# STML451RE_Buck_HSI.net
KiCad netlist of a schematic drawn in EAGLE
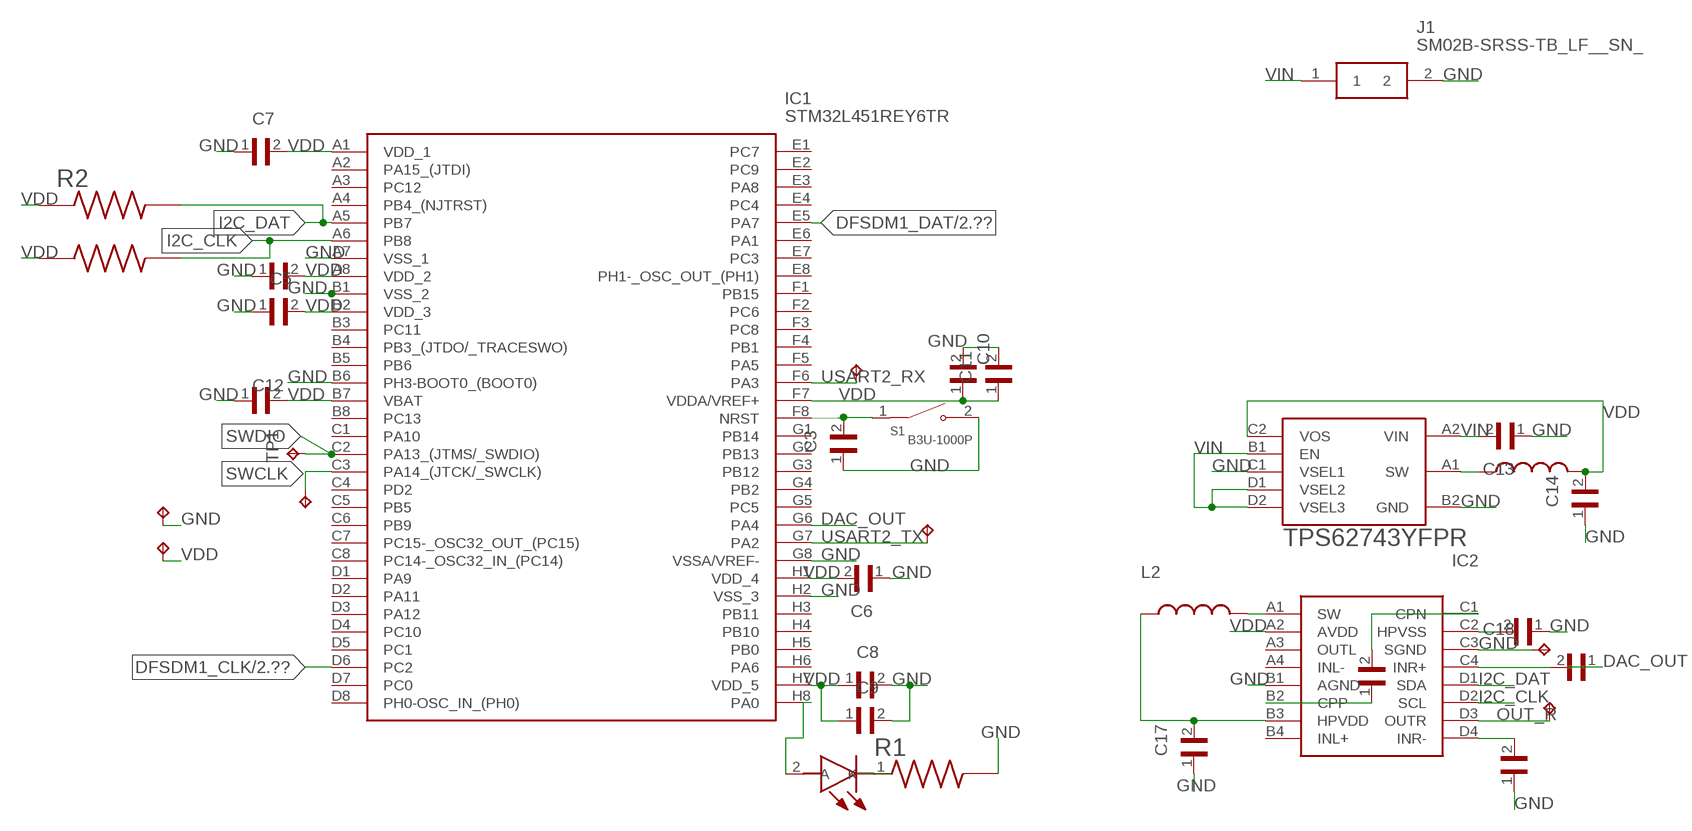
[diagram p0: schematic, sheet 1]
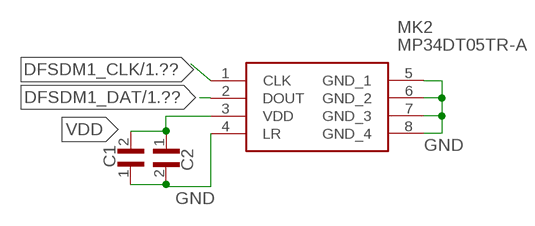
[diagram p1: schematic, sheet 2]

(export (version "E")
  (design (tool "Eeschema 10.0.6"))
  (components
    (comp (ref "C3")
      (value "GRM033C80J104KE15D")
      (footprint "eagle-import:CAPC0603X33N")
      (fields (field (name "DIGI-KEY_PART_NUMBER") "490-10390-1-ND") (field (name "MF") "Murata Electronics"))
      (libsource (lib "eagle-import") (part "GRM033C80J104KE15D"))
    )
    (comp (ref "C4")
      (value "GRM033C80J104KE15D")
      (footprint "eagle-import:CAPC0603X33N")
      (fields (field (name "DIGI-KEY_PART_NUMBER") "490-10390-1-ND") (field (name "MF") "Murata Electronics"))
      (libsource (lib "eagle-import") (part "GRM033C80J104KE15D"))
    )
    (comp (ref "C5")
      (value "GRM033C80J104KE15D")
      (footprint "eagle-import:CAPC0603X33N")
      (fields (field (name "DIGI-KEY_PART_NUMBER") "490-10390-1-ND") (field (name "MF") "Murata Electronics"))
      (libsource (lib "eagle-import") (part "GRM033C80J104KE15D"))
    )
    (comp (ref "C6")
      (value "GRM033C80J104KE15D")
      (footprint "eagle-import:CAPC0603X33N")
      (fields (field (name "DIGI-KEY_PART_NUMBER") "490-10390-1-ND") (field (name "MF") "Murata Electronics"))
      (libsource (lib "eagle-import") (part "GRM033C80J104KE15D"))
    )
    (comp (ref "C7")
      (value "GRM033C80J104KE15D")
      (footprint "eagle-import:CAPC0603X33N")
      (fields (field (name "DIGI-KEY_PART_NUMBER") "490-10390-1-ND") (field (name "MF") "Murata Electronics"))
      (libsource (lib "eagle-import") (part "GRM033C80J104KE15D"))
    )
    (comp (ref "C8")
      (value "GRM033C80J104KE15D")
      (footprint "eagle-import:CAPC0603X33N")
      (fields (field (name "DIGI-KEY_PART_NUMBER") "490-10390-1-ND") (field (name "MF") "Murata Electronics"))
      (libsource (lib "eagle-import") (part "GRM033C80J104KE15D"))
    )
    (comp (ref "C9")
      (value "GRM155R60J475ME47D")
      (footprint "eagle-import:CAPC1005X60N")
      (fields (field (name "DIGI-KEY_PART_NUMBER") "490-5915-1-ND") (field (name "MF") "Murata"))
      (libsource (lib "eagle-import") (part "GRM155R60J475ME47D"))
    )
    (comp (ref "C10")
      (value "GRM033C80J104KE15D")
      (footprint "eagle-import:CAPC0603X33N")
      (fields (field (name "DIGI-KEY_PART_NUMBER") "490-10390-1-ND") (field (name "MF") "Murata Electronics"))
      (libsource (lib "eagle-import") (part "GRM033C80J104KE15D"))
    )
    (comp (ref "C11")
      (value "JMK105C6105KV-F")
      (footprint "eagle-import:CAPC1005X55N")
      (fields (field (name "DIGI-KEY_PART_NUMBER") "587-3381-1-ND") (field (name "MF") "Taiyo Yuden"))
      (libsource (lib "eagle-import") (part "JMK105C6105KV-F"))
    )
    (comp (ref "C12")
      (value "GRM033C80J104KE15D")
      (footprint "eagle-import:CAPC0603X33N")
      (fields (field (name "DIGI-KEY_PART_NUMBER") "490-10390-1-ND") (field (name "MF") "Murata Electronics"))
      (libsource (lib "eagle-import") (part "GRM033C80J104KE15D"))
    )
    (comp (ref "C13")
      (value "GRM155R60J475ME47D")
      (footprint "eagle-import:CAPC1005X60N")
      (fields (field (name "DIGI-KEY_PART_NUMBER") "490-5915-1-ND") (field (name "MF") "Murata"))
      (libsource (lib "eagle-import") (part "GRM155R60J475ME47D"))
    )
    (comp (ref "C14")
      (value "GRM155R60J106ME15D")
      (footprint "eagle-import:CAPC1005X65N")
      (fields (field (name "DIGI-KEY_PART_NUMBER") "490-13238-1-ND") (field (name "MF") "Murata"))
      (libsource (lib "eagle-import") (part "GRM155R60J106ME15D"))
    )
    (comp (ref "C17")
      (value "GRM155R60J225KE95D")
      (footprint "eagle-import:CAPC1005X55N")
      (fields (field (name "DIGI-KEY_PART_NUMBER") "490-12532-1-ND") (field (name "MF") "Murata"))
      (libsource (lib "eagle-import") (part "GRM155R60J225KE95D"))
    )
    (comp (ref "C18")
      (value "GRM155R60J225KE95D")
      (footprint "eagle-import:CAPC1005X55N")
      (fields (field (name "DIGI-KEY_PART_NUMBER") "490-12532-1-ND") (field (name "MF") "Murata"))
      (libsource (lib "eagle-import") (part "GRM155R60J225KE95D"))
    )
    (comp (ref "C19")
      (value "JMK105C6105KV-F")
      (footprint "eagle-import:CAPC1005X55N")
      (fields (field (name "DIGI-KEY_PART_NUMBER") "587-3381-1-ND") (field (name "MF") "Taiyo Yuden"))
      (libsource (lib "eagle-import") (part "JMK105C6105KV-F"))
    )
    (comp (ref "C20")
      (value "JMK105C6105KV-F")
      (footprint "eagle-import:CAPC1005X55N")
      (fields (field (name "DIGI-KEY_PART_NUMBER") "587-3381-1-ND") (field (name "MF") "Taiyo Yuden"))
      (libsource (lib "eagle-import") (part "JMK105C6105KV-F"))
    )
    (comp (ref "C21")
      (value "JMK105C6105KV-F")
      (footprint "eagle-import:CAPC1005X55N")
      (fields (field (name "DIGI-KEY_PART_NUMBER") "587-3381-1-ND") (field (name "MF") "Taiyo Yuden"))
      (libsource (lib "eagle-import") (part "JMK105C6105KV-F"))
    )
    (comp (ref "IC1")
      (value "STM32L451REY6TR")
      (footprint "eagle-import:BGA64C40P8X8_336X366X58")
      (fields (field (name "MOUSER_PART_NUMBER") "511-STM32L451REY6TR"))
      (libsource (lib "eagle-import") (part "STM32L451REY6TR"))
    )
    (comp (ref "IC2")
      (value "TPA6140A2YFFT")
      (footprint "eagle-import:BGA16C40P4X4_156X156X63")
      (fields (field (name "MOUSER_PART_NUMBER") "595-TPA6140A2YFFT"))
      (libsource (lib "eagle-import") (part "TPA6140A2YFFT"))
    )
    (comp (ref "J1")
      (value "SM02B-SRSS-TB_LF__SN_")
      (footprint "eagle-import:SM02B-SRSS-TB")
      (fields (field (name "ARROW_PART_NUMBER") "SM02B-SRSS-TB(LF)(SN)"))
      (libsource (lib "eagle-import") (part "SM02B-SRSS-TB_LF__SN_"))
    )
    (comp (ref "L1")
      (value "1285AS-H-2R2M=P2")
      (footprint "eagle-import:INDC2016X100N")
      (fields (field (name "DIGI-KEY_PART_NUMBER") "490-10600-1-ND") (field (name "MF") "Murata Electronics"))
      (libsource (lib "eagle-import") (part "1285AS-H-2R2M=P2"))
    )
    (comp (ref "L2")
      (value "LQM21PN2R2MC0D")
      (footprint "eagle-import:INDC2012X55N")
      (fields (field (name "DIGI-KEY_PART_NUMBER") "490-4994-1-ND") (field (name "MF") "Murata"))
      (libsource (lib "eagle-import") (part "LQM21PN2R2MC0D"))
    )
    (comp (ref "LED1")
      (value "VLMS1500-GS08")
      (footprint "eagle-import:VLMG1500GS08")
      (fields (field (name "MOUSER_PART_NUMBER") "78-VLMS1500-GS08"))
      (libsource (lib "eagle-import") (part "VLMS1500-GS08"))
    )
    (comp (ref "R1")
      (value "CRCW02012K20FKED")
      (footprint "eagle-import:RESC0603X28N")
      (fields (field (name "DIGI-KEY_PART_NUMBER") "541-2.20KAABCT-ND") (field (name "MF") "Vishay"))
      (libsource (lib "eagle-import") (part "CRCW02012K20FKED"))
    )
    (comp (ref "R2")
      (value "ERA-2AEB122X")
      (footprint "eagle-import:RESC1005X40N")
      (fields (field (name "DIGI-KEY_PART_NUMBER") "P1.2KDCCT-ND") (field (name "MF") "Panasonic"))
      (libsource (lib "eagle-import") (part "ERA-2AEB122X"))
    )
    (comp (ref "R3")
      (value "ERA-2AEB122X")
      (footprint "eagle-import:RESC1005X40N")
      (fields (field (name "DIGI-KEY_PART_NUMBER") "P1.2KDCCT-ND") (field (name "MF") "Panasonic"))
      (libsource (lib "eagle-import") (part "ERA-2AEB122X"))
    )
    (comp (ref "S1")
      (value "B3U-1000P")
      (footprint "eagle-import:SW_B3U-1000P")
      (fields (field (name "DIGI-KEY_PART_NUMBER") "SW1020CT-ND") (field (name "MF") "Omron"))
      (libsource (lib "eagle-import") (part "B3U-1000P"))
    )
    (comp (ref "TP1")
      (value "TPTP11R")
      (footprint "eagle-import:TP11R")
      (libsource (lib "eagle-import") (part "TPTP11R"))
    )
    (comp (ref "TP2")
      (value "TPTP11R")
      (footprint "eagle-import:TP11R")
      (libsource (lib "eagle-import") (part "TPTP11R"))
    )
    (comp (ref "TP3")
      (value "TPTP11R")
      (footprint "eagle-import:TP11R")
      (libsource (lib "eagle-import") (part "TPTP11R"))
    )
    (comp (ref "TP4")
      (value "TPTP11R")
      (footprint "eagle-import:TP11R")
      (libsource (lib "eagle-import") (part "TPTP11R"))
    )
    (comp (ref "TP5")
      (value "TPTP11R")
      (footprint "eagle-import:TP11R")
      (libsource (lib "eagle-import") (part "TPTP11R"))
    )
    (comp (ref "TP6")
      (value "TPTP11R")
      (footprint "eagle-import:TP11R")
      (libsource (lib "eagle-import") (part "TPTP11R"))
    )
    (comp (ref "TP7")
      (value "TPTP11R")
      (footprint "eagle-import:TP11R")
      (libsource (lib "eagle-import") (part "TPTP11R"))
    )
    (comp (ref "TP8")
      (value "TPTP11R")
      (footprint "eagle-import:TP11R")
      (libsource (lib "eagle-import") (part "TPTP11R"))
    )
    (comp (ref "U1")
      (value "TPS62743YFPR")
      (footprint "eagle-import:BGA8N40P2X4_87X156X50")
      (fields (field (name "DIGI-KEY_PART_NUMBER") "296-42392-1-ND") (field (name "MF") "Texas Instruments"))
      (libsource (lib "eagle-import") (part "TPS62743YFPR"))
    )
    (comp (ref "C1")
      (value "GRM033C80J104KE15D")
      (footprint "eagle-import:CAPC0603X33N")
      (fields (field (name "DIGI-KEY_PART_NUMBER") "490-10390-1-ND") (field (name "MF") "Murata Electronics"))
      (libsource (lib "eagle-import") (part "GRM033C80J104KE15D"))
    )
    (comp (ref "C2")
      (value "JMK105C6105KV-F")
      (footprint "eagle-import:CAPC1005X55N")
      (fields (field (name "DIGI-KEY_PART_NUMBER") "587-3381-1-ND") (field (name "MF") "Taiyo Yuden"))
      (libsource (lib "eagle-import") (part "JMK105C6105KV-F"))
    )
    (comp (ref "MK2")
      (value "MP34DT05TR-A")
      (footprint "eagle-import:MP34DT05TRA")
      (fields (field (name "MOUSER_PART_NUMBER") "511-MP34DT05TR-A"))
      (libsource (lib "eagle-import") (part "MP34DT05TR-A"))
    )
  )
  (nets
    (net (code "1") (name "DAC_OUT") (class "Default")
      (node (ref "C21") (pin "1") (pinfunction "1_1") (pintype "passive"))
      (node (ref "IC1") (pin "G6") (pinfunction "PA4_G6") (pintype "bidirectional"))
    )
    (net (code "2") (name "DFSDM1_CLK") (class "Default")
      (node (ref "IC1") (pin "D6") (pinfunction "PC2_D6") (pintype "bidirectional"))
      (node (ref "MK2") (pin "1") (pinfunction "CLK_1") (pintype "bidirectional"))
    )
    (net (code "3") (name "DFSDM1_DAT") (class "Default")
      (node (ref "IC1") (pin "E5") (pinfunction "PA7_E5") (pintype "bidirectional"))
      (node (ref "MK2") (pin "2") (pinfunction "DOUT_2") (pintype "bidirectional"))
    )
    (net (code "4") (name "GND") (class "Default")
      (node (ref "C1") (pin "1") (pinfunction "1_1") (pintype "passive"))
      (node (ref "C10") (pin "2") (pinfunction "2_2") (pintype "passive"))
      (node (ref "C11") (pin "2") (pinfunction "2_2") (pintype "passive"))
      (node (ref "C12") (pin "1") (pinfunction "1_1") (pintype "passive"))
      (node (ref "C13") (pin "1") (pinfunction "1_1") (pintype "passive"))
      (node (ref "C14") (pin "1") (pinfunction "1_1") (pintype "passive"))
      (node (ref "C17") (pin "1") (pinfunction "1_1") (pintype "passive"))
      (node (ref "C18") (pin "1") (pinfunction "1_1") (pintype "passive"))
      (node (ref "C2") (pin "2") (pinfunction "2_2") (pintype "passive"))
      (node (ref "C20") (pin "1") (pinfunction "1_1") (pintype "passive"))
      (node (ref "C3") (pin "1") (pinfunction "1_1") (pintype "passive"))
      (node (ref "C4") (pin "1") (pinfunction "1_1") (pintype "passive"))
      (node (ref "C5") (pin "1") (pinfunction "1_1") (pintype "passive"))
      (node (ref "C6") (pin "1") (pinfunction "1_1") (pintype "passive"))
      (node (ref "C7") (pin "1") (pinfunction "1_1") (pintype "passive"))
      (node (ref "C8") (pin "2") (pinfunction "2_2") (pintype "passive"))
      (node (ref "C9") (pin "2") (pinfunction "2_2") (pintype "passive"))
      (node (ref "IC1") (pin "A7") (pinfunction "VSS_1_A7") (pintype "bidirectional"))
      (node (ref "IC1") (pin "B1") (pinfunction "VSS_2_B1") (pintype "bidirectional"))
      (node (ref "IC1") (pin "B6") (pinfunction "PH3-BOOT0_(BOOT0)_B6") (pintype "bidirectional"))
      (node (ref "IC1") (pin "G8") (pinfunction "VSSA/VREF-_G8") (pintype "bidirectional"))
      (node (ref "IC1") (pin "H2") (pinfunction "VSS_3_H2") (pintype "bidirectional"))
      (node (ref "IC2") (pin "B1") (pinfunction "AGND_B1") (pintype "bidirectional"))
      (node (ref "IC2") (pin "C3") (pinfunction "SGND_C3") (pintype "bidirectional"))
      (node (ref "J1") (pin "2") (pinfunction "2_2") (pintype "bidirectional"))
      (node (ref "MK2") (pin "4") (pinfunction "LR_4") (pintype "bidirectional"))
      (node (ref "MK2") (pin "5") (pinfunction "GND_1_5") (pintype "bidirectional"))
      (node (ref "MK2") (pin "6") (pinfunction "GND_2_6") (pintype "bidirectional"))
      (node (ref "MK2") (pin "7") (pinfunction "GND_3_7") (pintype "bidirectional"))
      (node (ref "MK2") (pin "8") (pinfunction "GND_4_8") (pintype "bidirectional"))
      (node (ref "R1") (pin "2") (pinfunction "2_2") (pintype "passive"))
      (node (ref "S1") (pin "2") (pinfunction "2_2") (pintype "passive"))
      (node (ref "TP3") (pin "TP") (pinfunction "TP_TP") (pintype "input"))
      (node (ref "TP8") (pin "TP") (pinfunction "TP_TP") (pintype "input"))
      (node (ref "U1") (pin "B2") (pinfunction "GND_B2") (pintype "passive"))
      (node (ref "U1") (pin "C1") (pinfunction "VSEL1_C1") (pintype "input"))
    )
    (net (code "5") (name "I2C_CLK") (class "Default")
      (node (ref "IC1") (pin "A6") (pinfunction "PB8_A6") (pintype "bidirectional"))
      (node (ref "IC2") (pin "D2") (pinfunction "SCL_D2") (pintype "bidirectional"))
      (node (ref "R3") (pin "2") (pinfunction "2_2") (pintype "passive"))
    )
    (net (code "6") (name "I2C_DAT") (class "Default")
      (node (ref "IC1") (pin "A5") (pinfunction "PB7_A5") (pintype "bidirectional"))
      (node (ref "IC2") (pin "D1") (pinfunction "SDA_D1") (pintype "bidirectional"))
      (node (ref "R2") (pin "2") (pinfunction "2_2") (pintype "passive"))
    )
    (net (code "7") (name "Net-(C3-Pad2)") (class "Default")
      (node (ref "C3") (pin "2") (pinfunction "2_2") (pintype "passive"))
      (node (ref "S1") (pin "1") (pinfunction "1_1") (pintype "passive"))
    )
    (net (code "8") (name "Net-(IC1-PA0)") (class "Default")
      (node (ref "IC1") (pin "H8") (pinfunction "PA0_H8") (pintype "bidirectional"))
      (node (ref "LED1") (pin "2") (pinfunction "A_2") (pintype "bidirectional"))
    )
    (net (code "9") (name "Net-(IC2-CPN)") (class "Default")
      (node (ref "C19") (pin "2") (pinfunction "2_2") (pintype "passive"))
      (node (ref "IC2") (pin "C1") (pinfunction "CPN_C1") (pintype "bidirectional"))
    )
    (net (code "10") (name "Net-(IC2-CPP)") (class "Default")
      (node (ref "C19") (pin "1") (pinfunction "1_1") (pintype "passive"))
      (node (ref "IC2") (pin "B2") (pinfunction "CPP_B2") (pintype "bidirectional"))
    )
    (net (code "11") (name "Net-(IC2-HPVDD)") (class "Default")
      (node (ref "C17") (pin "2") (pinfunction "2_2") (pintype "passive"))
      (node (ref "IC2") (pin "B3") (pinfunction "HPVDD_B3") (pintype "bidirectional"))
      (node (ref "L2") (pin "1") (pinfunction "1_1") (pintype "passive"))
    )
    (net (code "12") (name "Net-(IC2-HPVSS)") (class "Default")
      (node (ref "C18") (pin "2") (pinfunction "2_2") (pintype "passive"))
      (node (ref "IC2") (pin "C2") (pinfunction "HPVSS_C2") (pintype "bidirectional"))
    )
    (net (code "13") (name "Net-(IC2-INR+)") (class "Default")
      (node (ref "C21") (pin "2") (pinfunction "2_2") (pintype "passive"))
      (node (ref "IC2") (pin "C4") (pinfunction "INR+_C4") (pintype "bidirectional"))
    )
    (net (code "14") (name "Net-(IC2-INR-)") (class "Default")
      (node (ref "C20") (pin "2") (pinfunction "2_2") (pintype "passive"))
      (node (ref "IC2") (pin "D4") (pinfunction "INR-_D4") (pintype "bidirectional"))
    )
    (net (code "15") (name "Net-(IC2-SW)") (class "Default")
      (node (ref "IC2") (pin "A1") (pinfunction "SW_A1") (pintype "bidirectional"))
      (node (ref "L2") (pin "2") (pinfunction "2_2") (pintype "passive"))
    )
    (net (code "16") (name "Net-(LED1-K)") (class "Default")
      (node (ref "LED1") (pin "1") (pinfunction "K_1") (pintype "bidirectional"))
      (node (ref "R1") (pin "1") (pinfunction "1_1") (pintype "passive"))
    )
    (net (code "17") (name "Net-(U1-SW)") (class "Default")
      (node (ref "L1") (pin "1") (pinfunction "1_1") (pintype "passive"))
      (node (ref "U1") (pin "A1") (pinfunction "SW_A1") (pintype "output"))
    )
    (net (code "18") (name "OUT_R") (class "Default")
      (node (ref "IC2") (pin "D3") (pinfunction "OUTR_D3") (pintype "bidirectional"))
      (node (ref "TP7") (pin "TP") (pinfunction "TP_TP") (pintype "input"))
    )
    (net (code "19") (name "SWCLK") (class "Default")
      (node (ref "IC1") (pin "C3") (pinfunction "PA14_(JTCK/_SWCLK)_C3") (pintype "bidirectional"))
      (node (ref "TP2") (pin "TP") (pinfunction "TP_TP") (pintype "input"))
    )
    (net (code "20") (name "SWDIO") (class "Default")
      (node (ref "IC1") (pin "C2") (pinfunction "PA13_(JTMS/_SWDIO)_C2") (pintype "bidirectional"))
      (node (ref "TP1") (pin "TP") (pinfunction "TP_TP") (pintype "input"))
    )
    (net (code "21") (name "USART2_RX") (class "Default")
      (node (ref "IC1") (pin "F6") (pinfunction "PA3_F6") (pintype "bidirectional"))
      (node (ref "TP6") (pin "TP") (pinfunction "TP_TP") (pintype "input"))
    )
    (net (code "22") (name "USART2_TX") (class "Default")
      (node (ref "IC1") (pin "G7") (pinfunction "PA2_G7") (pintype "bidirectional"))
      (node (ref "TP5") (pin "TP") (pinfunction "TP_TP") (pintype "input"))
    )
    (net (code "23") (name "VDD") (class "Default")
      (node (ref "C1") (pin "2") (pinfunction "2_2") (pintype "passive"))
      (node (ref "C10") (pin "1") (pinfunction "1_1") (pintype "passive"))
      (node (ref "C11") (pin "1") (pinfunction "1_1") (pintype "passive"))
      (node (ref "C12") (pin "2") (pinfunction "2_2") (pintype "passive"))
      (node (ref "C14") (pin "2") (pinfunction "2_2") (pintype "passive"))
      (node (ref "C2") (pin "1") (pinfunction "1_1") (pintype "passive"))
      (node (ref "C4") (pin "2") (pinfunction "2_2") (pintype "passive"))
      (node (ref "C5") (pin "2") (pinfunction "2_2") (pintype "passive"))
      (node (ref "C6") (pin "2") (pinfunction "2_2") (pintype "passive"))
      (node (ref "C7") (pin "2") (pinfunction "2_2") (pintype "passive"))
      (node (ref "C8") (pin "1") (pinfunction "1_1") (pintype "passive"))
      (node (ref "C9") (pin "1") (pinfunction "1_1") (pintype "passive"))
      (node (ref "IC1") (pin "A1") (pinfunction "VDD_1_A1") (pintype "bidirectional"))
      (node (ref "IC1") (pin "A8") (pinfunction "VDD_2_A8") (pintype "bidirectional"))
      (node (ref "IC1") (pin "B2") (pinfunction "VDD_3_B2") (pintype "bidirectional"))
      (node (ref "IC1") (pin "B7") (pinfunction "VBAT_B7") (pintype "bidirectional"))
      (node (ref "IC1") (pin "F7") (pinfunction "VDDA/VREF+_F7") (pintype "bidirectional"))
      (node (ref "IC1") (pin "H1") (pinfunction "VDD_4_H1") (pintype "bidirectional"))
      (node (ref "IC1") (pin "H7") (pinfunction "VDD_5_H7") (pintype "bidirectional"))
      (node (ref "IC2") (pin "A2") (pinfunction "AVDD_A2") (pintype "bidirectional"))
      (node (ref "L1") (pin "2") (pinfunction "2_2") (pintype "passive"))
      (node (ref "MK2") (pin "3") (pinfunction "VDD_3") (pintype "bidirectional"))
      (node (ref "R2") (pin "1") (pinfunction "1_1") (pintype "passive"))
      (node (ref "R3") (pin "1") (pinfunction "1_1") (pintype "passive"))
      (node (ref "TP4") (pin "TP") (pinfunction "TP_TP") (pintype "input"))
      (node (ref "U1") (pin "C2") (pinfunction "VOS_C2") (pintype "input"))
    )
    (net (code "24") (name "VIN") (class "Default")
      (node (ref "C13") (pin "2") (pinfunction "2_2") (pintype "passive"))
      (node (ref "J1") (pin "1") (pinfunction "1_1") (pintype "bidirectional"))
      (node (ref "U1") (pin "A2") (pinfunction "VIN_A2") (pintype "power_in"))
      (node (ref "U1") (pin "B1") (pinfunction "EN_B1") (pintype "input"))
      (node (ref "U1") (pin "D1") (pinfunction "VSEL2_D1") (pintype "input"))
      (node (ref "U1") (pin "D2") (pinfunction "VSEL3_D2") (pintype "input"))
    )
    (net (code "25") (name "unconnected-(IC1-NRST-PadF8)") (class "Default")
      (node (ref "IC1") (pin "F8") (pinfunction "NRST_F8") (pintype "bidirectional"))
    )
    (net (code "26") (name "unconnected-(IC1-PA1-PadE6)") (class "Default")
      (node (ref "IC1") (pin "E6") (pinfunction "PA1_E6") (pintype "bidirectional"))
    )
    (net (code "27") (name "unconnected-(IC1-PA5-PadF5)") (class "Default")
      (node (ref "IC1") (pin "F5") (pinfunction "PA5_F5") (pintype "bidirectional"))
    )
    (net (code "28") (name "unconnected-(IC1-PA6-PadH6)") (class "Default")
      (node (ref "IC1") (pin "H6") (pinfunction "PA6_H6") (pintype "bidirectional"))
    )
    (net (code "29") (name "unconnected-(IC1-PA8-PadE3)") (class "Default")
      (node (ref "IC1") (pin "E3") (pinfunction "PA8_E3") (pintype "bidirectional"))
    )
    (net (code "30") (name "unconnected-(IC1-PA9-PadD1)") (class "Default")
      (node (ref "IC1") (pin "D1") (pinfunction "PA9_D1") (pintype "bidirectional"))
    )
    (net (code "31") (name "unconnected-(IC1-PA10-PadC1)") (class "Default")
      (node (ref "IC1") (pin "C1") (pinfunction "PA10_C1") (pintype "bidirectional"))
    )
    (net (code "32") (name "unconnected-(IC1-PA11-PadD2)") (class "Default")
      (node (ref "IC1") (pin "D2") (pinfunction "PA11_D2") (pintype "bidirectional"))
    )
    (net (code "33") (name "unconnected-(IC1-PA12-PadD3)") (class "Default")
      (node (ref "IC1") (pin "D3") (pinfunction "PA12_D3") (pintype "bidirectional"))
    )
    (net (code "34") (name "unconnected-(IC1-PA15_(JTDI)-PadA2)") (class "Default")
      (node (ref "IC1") (pin "A2") (pinfunction "PA15_(JTDI)_A2") (pintype "bidirectional"))
    )
    (net (code "35") (name "unconnected-(IC1-PB0-PadH5)") (class "Default")
      (node (ref "IC1") (pin "H5") (pinfunction "PB0_H5") (pintype "bidirectional"))
    )
    (net (code "36") (name "unconnected-(IC1-PB1-PadF4)") (class "Default")
      (node (ref "IC1") (pin "F4") (pinfunction "PB1_F4") (pintype "bidirectional"))
    )
    (net (code "37") (name "unconnected-(IC1-PB2-PadG4)") (class "Default")
      (node (ref "IC1") (pin "G4") (pinfunction "PB2_G4") (pintype "bidirectional"))
    )
    (net (code "38") (name "unconnected-(IC1-PB3_(JTDO{slash}_TRACESWO)-PadB4)") (class "Default")
      (node (ref "IC1") (pin "B4") (pinfunction "PB3_(JTDO/_TRACESWO)_B4") (pintype "bidirectional"))
    )
    (net (code "39") (name "unconnected-(IC1-PB4_(NJTRST)-PadA4)") (class "Default")
      (node (ref "IC1") (pin "A4") (pinfunction "PB4_(NJTRST)_A4") (pintype "bidirectional"))
    )
    (net (code "40") (name "unconnected-(IC1-PB5-PadC5)") (class "Default")
      (node (ref "IC1") (pin "C5") (pinfunction "PB5_C5") (pintype "bidirectional"))
    )
    (net (code "41") (name "unconnected-(IC1-PB6-PadB5)") (class "Default")
      (node (ref "IC1") (pin "B5") (pinfunction "PB6_B5") (pintype "bidirectional"))
    )
    (net (code "42") (name "unconnected-(IC1-PB9-PadC6)") (class "Default")
      (node (ref "IC1") (pin "C6") (pinfunction "PB9_C6") (pintype "bidirectional"))
    )
    (net (code "43") (name "unconnected-(IC1-PB10-PadH4)") (class "Default")
      (node (ref "IC1") (pin "H4") (pinfunction "PB10_H4") (pintype "bidirectional"))
    )
    (net (code "44") (name "unconnected-(IC1-PB11-PadH3)") (class "Default")
      (node (ref "IC1") (pin "H3") (pinfunction "PB11_H3") (pintype "bidirectional"))
    )
    (net (code "45") (name "unconnected-(IC1-PB12-PadG3)") (class "Default")
      (node (ref "IC1") (pin "G3") (pinfunction "PB12_G3") (pintype "bidirectional"))
    )
    (net (code "46") (name "unconnected-(IC1-PB13-PadG2)") (class "Default")
      (node (ref "IC1") (pin "G2") (pinfunction "PB13_G2") (pintype "bidirectional"))
    )
    (net (code "47") (name "unconnected-(IC1-PB14-PadG1)") (class "Default")
      (node (ref "IC1") (pin "G1") (pinfunction "PB14_G1") (pintype "bidirectional"))
    )
    (net (code "48") (name "unconnected-(IC1-PB15-PadF1)") (class "Default")
      (node (ref "IC1") (pin "F1") (pinfunction "PB15_F1") (pintype "bidirectional"))
    )
    (net (code "49") (name "unconnected-(IC1-PC0-PadD7)") (class "Default")
      (node (ref "IC1") (pin "D7") (pinfunction "PC0_D7") (pintype "bidirectional"))
    )
    (net (code "50") (name "unconnected-(IC1-PC1-PadD5)") (class "Default")
      (node (ref "IC1") (pin "D5") (pinfunction "PC1_D5") (pintype "bidirectional"))
    )
    (net (code "51") (name "unconnected-(IC1-PC3-PadE7)") (class "Default")
      (node (ref "IC1") (pin "E7") (pinfunction "PC3_E7") (pintype "bidirectional"))
    )
    (net (code "52") (name "unconnected-(IC1-PC4-PadE4)") (class "Default")
      (node (ref "IC1") (pin "E4") (pinfunction "PC4_E4") (pintype "bidirectional"))
    )
    (net (code "53") (name "unconnected-(IC1-PC5-PadG5)") (class "Default")
      (node (ref "IC1") (pin "G5") (pinfunction "PC5_G5") (pintype "bidirectional"))
    )
    (net (code "54") (name "unconnected-(IC1-PC6-PadF2)") (class "Default")
      (node (ref "IC1") (pin "F2") (pinfunction "PC6_F2") (pintype "bidirectional"))
    )
    (net (code "55") (name "unconnected-(IC1-PC7-PadE1)") (class "Default")
      (node (ref "IC1") (pin "E1") (pinfunction "PC7_E1") (pintype "bidirectional"))
    )
    (net (code "56") (name "unconnected-(IC1-PC8-PadF3)") (class "Default")
      (node (ref "IC1") (pin "F3") (pinfunction "PC8_F3") (pintype "bidirectional"))
    )
    (net (code "57") (name "unconnected-(IC1-PC9-PadE2)") (class "Default")
      (node (ref "IC1") (pin "E2") (pinfunction "PC9_E2") (pintype "bidirectional"))
    )
    (net (code "58") (name "unconnected-(IC1-PC10-PadD4)") (class "Default")
      (node (ref "IC1") (pin "D4") (pinfunction "PC10_D4") (pintype "bidirectional"))
    )
    (net (code "59") (name "unconnected-(IC1-PC11-PadB3)") (class "Default")
      (node (ref "IC1") (pin "B3") (pinfunction "PC11_B3") (pintype "bidirectional"))
    )
    (net (code "60") (name "unconnected-(IC1-PC12-PadA3)") (class "Default")
      (node (ref "IC1") (pin "A3") (pinfunction "PC12_A3") (pintype "bidirectional"))
    )
    (net (code "61") (name "unconnected-(IC1-PC13-PadB8)") (class "Default")
      (node (ref "IC1") (pin "B8") (pinfunction "PC13_B8") (pintype "bidirectional"))
    )
    (net (code "62") (name "unconnected-(IC1-PC14-_OSC32_IN_(PC14)-PadC8)") (class "Default")
      (node (ref "IC1") (pin "C8") (pinfunction "PC14-_OSC32_IN_(PC14)_C8") (pintype "bidirectional"))
    )
    (net (code "63") (name "unconnected-(IC1-PC15-_OSC32_OUT_(PC15)-PadC7)") (class "Default")
      (node (ref "IC1") (pin "C7") (pinfunction "PC15-_OSC32_OUT_(PC15)_C7") (pintype "bidirectional"))
    )
    (net (code "64") (name "unconnected-(IC1-PD2-PadC4)") (class "Default")
      (node (ref "IC1") (pin "C4") (pinfunction "PD2_C4") (pintype "bidirectional"))
    )
    (net (code "65") (name "unconnected-(IC1-PH0-OSC_IN_(PH0)-PadD8)") (class "Default")
      (node (ref "IC1") (pin "D8") (pinfunction "PH0-OSC_IN_(PH0)_D8") (pintype "bidirectional"))
    )
    (net (code "66") (name "unconnected-(IC1-PH1-_OSC_OUT_(PH1)-PadE8)") (class "Default")
      (node (ref "IC1") (pin "E8") (pinfunction "PH1-_OSC_OUT_(PH1)_E8") (pintype "bidirectional"))
    )
    (net (code "67") (name "unconnected-(IC2-INL+-PadB4)") (class "Default")
      (node (ref "IC2") (pin "B4") (pinfunction "INL+_B4") (pintype "bidirectional"))
    )
    (net (code "68") (name "unconnected-(IC2-INL--PadA4)") (class "Default")
      (node (ref "IC2") (pin "A4") (pinfunction "INL-_A4") (pintype "bidirectional"))
    )
    (net (code "69") (name "unconnected-(IC2-OUTL-PadA3)") (class "Default")
      (node (ref "IC2") (pin "A3") (pinfunction "OUTL_A3") (pintype "bidirectional"))
    )
  )
)
